# BSIextensionBoard.net
KiCad netlist of a schematic drawn in EAGLE
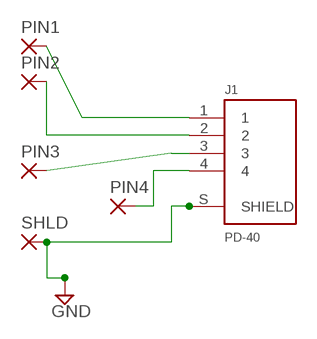
[diagram p0: schematic, sheet 1]

(export (version "E")
  (design (tool "Eeschema 10.0.6"))
  (components
    (comp (ref "J1")
      (value "PD-40")
      (footprint "eagle-import:CUI_PD-40")
      (fields (field (name "MF") "CUI Inc"))
      (libsource (lib "eagle-import") (part "PD-40"))
    )
    (comp (ref "PIN1")
      (value "3,81/1,4")
      (footprint "eagle-import:3,81_1,4")
      (libsource (lib "eagle-import") (part "3,81/1,4"))
    )
    (comp (ref "PIN2")
      (value "3,81/1,4")
      (footprint "eagle-import:3,81_1,4")
      (libsource (lib "eagle-import") (part "3,81/1,4"))
    )
    (comp (ref "PIN3")
      (value "3,81/1,4")
      (footprint "eagle-import:3,81_1,4")
      (libsource (lib "eagle-import") (part "3,81/1,4"))
    )
    (comp (ref "PIN4")
      (value "3,81/1,4")
      (footprint "eagle-import:3,81_1,4")
      (libsource (lib "eagle-import") (part "3,81/1,4"))
    )
    (comp (ref "SHLD")
      (value "3,81/1,4")
      (footprint "eagle-import:3,81_1,4")
      (libsource (lib "eagle-import") (part "3,81/1,4"))
    )
  )
  (nets
    (net (code "1") (name "GND") (class "Default")
      (node (ref "J1") (pin "S") (pinfunction "SHIELD_S") (pintype "passive"))
      (node (ref "SHLD") (pin "1") (pinfunction "P_1") (pintype "passive"))
    )
    (net (code "2") (name "Net-(PIN1-P)") (class "Default")
      (node (ref "J1") (pin "1") (pinfunction "1_1") (pintype "passive"))
      (node (ref "PIN1") (pin "1") (pinfunction "P_1") (pintype "passive"))
    )
    (net (code "3") (name "Net-(PIN2-P)") (class "Default")
      (node (ref "J1") (pin "2") (pinfunction "2_2") (pintype "passive"))
      (node (ref "PIN2") (pin "1") (pinfunction "P_1") (pintype "passive"))
    )
    (net (code "4") (name "Net-(PIN3-P)") (class "Default")
      (node (ref "J1") (pin "3") (pinfunction "3_3") (pintype "passive"))
      (node (ref "PIN3") (pin "1") (pinfunction "P_1") (pintype "passive"))
    )
    (net (code "5") (name "Net-(PIN4-P)") (class "Default")
      (node (ref "J1") (pin "4") (pinfunction "4_4") (pintype "passive"))
      (node (ref "PIN4") (pin "1") (pinfunction "P_1") (pintype "passive"))
    )
  )
)
